# Transistor_controlled_bell_switch.net
KiCad netlist of a schematic drawn in EAGLE
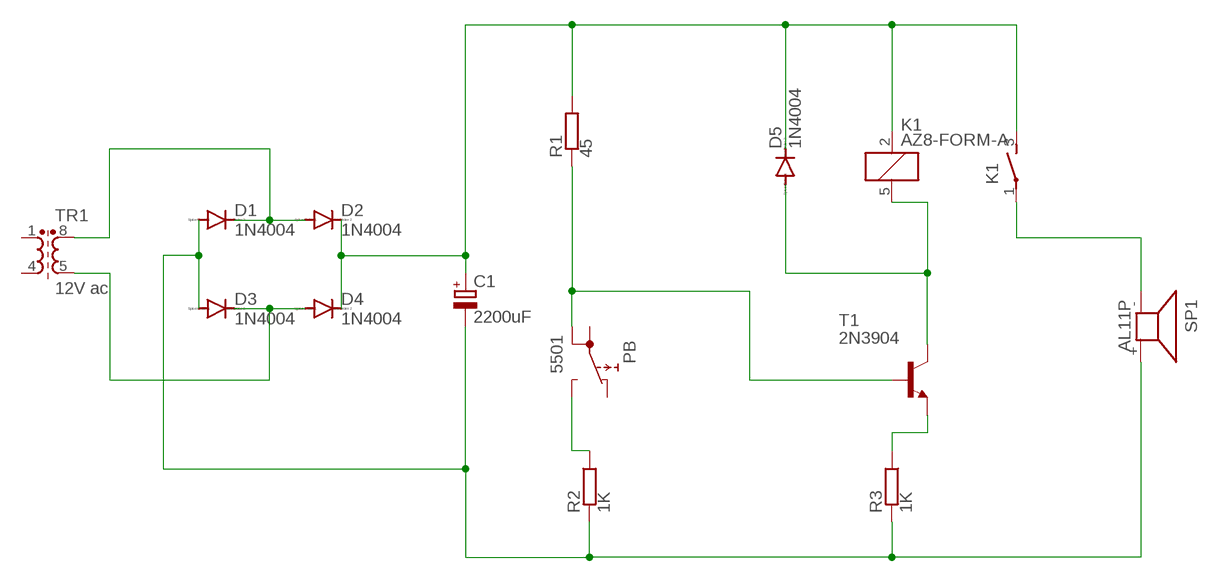
[diagram p0: schematic, sheet 1]

(export (version "E")
  (design (tool "Eeschema 10.0.6"))
  (components
    (comp (ref "C1")
      (value "2200uF")
      (footprint "eagle-import:085CS_1AR")
      (libsource (lib "eagle-import") (part "CPOL-EU085CS-1AR"))
    )
    (comp (ref "D1")
      (value "1N4004")
      (footprint "eagle-import:DO41-10")
      (libsource (lib "eagle-import") (part "1N4004"))
    )
    (comp (ref "D2")
      (value "1N4004")
      (footprint "eagle-import:DO41-10")
      (libsource (lib "eagle-import") (part "1N4004"))
    )
    (comp (ref "D3")
      (value "1N4004")
      (footprint "eagle-import:DO41-10")
      (libsource (lib "eagle-import") (part "1N4004"))
    )
    (comp (ref "D4")
      (value "1N4004")
      (footprint "eagle-import:DO41-10")
      (libsource (lib "eagle-import") (part "1N4004"))
    )
    (comp (ref "D5")
      (value "1N4004")
      (footprint "eagle-import:DO41-10")
      (libsource (lib "eagle-import") (part "1N4004"))
    )
    (comp (ref "K1")
      (value "AZ8-FORM-A")
      (footprint "eagle-import:AZ8")
      (libsource (lib "eagle-import") (part "AZ8-FORM-A"))
    )
    (comp (ref "PB")
      (value "5501")
      (footprint "eagle-import:5501")
      (libsource (lib "eagle-import") (part "55?01"))
    )
    (comp (ref "R1")
      (value "45")
      (footprint "eagle-import:PMD")
      (libsource (lib "eagle-import") (part "PMD"))
    )
    (comp (ref "R2")
      (value "1K")
      (footprint "eagle-import:PMD")
      (libsource (lib "eagle-import") (part "PMD"))
    )
    (comp (ref "R3")
      (value "1K")
      (footprint "eagle-import:PMD")
      (libsource (lib "eagle-import") (part "PMD"))
    )
    (comp (ref "SP1")
      (value "AL11P")
      (footprint "eagle-import:AL11P")
      (libsource (lib "eagle-import") (part "AL11P"))
    )
    (comp (ref "T1")
      (value "2N3904")
      (footprint "eagle-import:TO92")
      (libsource (lib "eagle-import") (part "2N3904"))
    )
    (comp (ref "TR1")
      (value "12V ac")
      (footprint "eagle-import:SM-R6")
      (libsource (lib "eagle-import") (part "SMR6-2W"))
    )
  )
  (nets
    (net (code "1") (name "Net-(D1-PadC)") (class "Default")
      (node (ref "D1") (pin "C") (pinfunction "C_C") (pintype "passive"))
      (node (ref "D2") (pin "A") (pinfunction "A_A") (pintype "passive"))
      (node (ref "TR1") (pin "8") (pinfunction "8_8") (pintype "passive"))
    )
    (net (code "2") (name "Net-(D3-PadC)") (class "Default")
      (node (ref "D3") (pin "C") (pinfunction "C_C") (pintype "passive"))
      (node (ref "D4") (pin "A") (pinfunction "A_A") (pintype "passive"))
      (node (ref "TR1") (pin "5") (pinfunction "5_5") (pintype "passive"))
    )
    (net (code "3") (name "Net-(K1A-P)") (class "Default")
      (node (ref "K1") (pin "1") (pinfunction "P_1") (pintype "passive"))
      (node (ref "SP1") (pin "-") (pinfunction "1_-") (pintype "passive"))
    )
    (net (code "4") (name "Net-(K1A-S)") (class "Default")
      (node (ref "C1") (pin "+") (pinfunction "+_+") (pintype "passive"))
      (node (ref "D2") (pin "C") (pinfunction "C_C") (pintype "passive"))
      (node (ref "D4") (pin "C") (pinfunction "C_C") (pintype "passive"))
      (node (ref "D5") (pin "C") (pinfunction "C_C") (pintype "passive"))
      (node (ref "K1") (pin "2") (pinfunction "1_2") (pintype "passive"))
      (node (ref "K1") (pin "3") (pinfunction "S_3") (pintype "passive"))
      (node (ref "R1") (pin "1") (pinfunction "1_1") (pintype "passive"))
    )
    (net (code "5") (name "Net-(K1B-2)") (class "Default")
      (node (ref "D5") (pin "A") (pinfunction "A_A") (pintype "passive"))
      (node (ref "K1") (pin "5") (pinfunction "2_5") (pintype "passive"))
      (node (ref "T1") (pin "1") (pinfunction "C_1") (pintype "passive"))
    )
    (net (code "6") (name "Net-(PB-PadNO)") (class "Default")
      (node (ref "PB") (pin "NO") (pinfunction "NO_NO") (pintype "passive"))
      (node (ref "R2") (pin "1") (pinfunction "1_1") (pintype "passive"))
    )
    (net (code "7") (name "Net-(SP1-2)") (class "Default")
      (node (ref "C1") (pin "-") (pinfunction "-_-") (pintype "passive"))
      (node (ref "D1") (pin "A") (pinfunction "A_A") (pintype "passive"))
      (node (ref "D3") (pin "A") (pinfunction "A_A") (pintype "passive"))
      (node (ref "R2") (pin "2") (pinfunction "2_2") (pintype "passive"))
      (node (ref "R3") (pin "2") (pinfunction "2_2") (pintype "passive"))
      (node (ref "SP1") (pin "+") (pinfunction "2_+") (pintype "passive"))
    )
    (net (code "8") (name "Net-(T1-B)") (class "Default")
      (node (ref "PB") (pin "1B") (pinfunction "1B_1B") (pintype "passive"))
      (node (ref "R1") (pin "2") (pinfunction "2_2") (pintype "passive"))
      (node (ref "T1") (pin "2") (pinfunction "B_2") (pintype "passive"))
    )
    (net (code "9") (name "Net-(T1-E)") (class "Default")
      (node (ref "R3") (pin "1") (pinfunction "1_1") (pintype "passive"))
      (node (ref "T1") (pin "3") (pinfunction "E_3") (pintype "passive"))
    )
    (net (code "10") (name "unconnected-(PB-Pad1A)") (class "Default")
      (node (ref "PB") (pin "1A") (pinfunction "1A_1A") (pintype "passive"))
    )
    (net (code "11") (name "unconnected-(PB-PadNC)") (class "Default")
      (node (ref "PB") (pin "NC") (pinfunction "NC_NC") (pintype "passive"))
    )
    (net (code "12") (name "unconnected-(TR1-Pad1)") (class "Default")
      (node (ref "TR1") (pin "1") (pinfunction "1_1") (pintype "passive"))
    )
    (net (code "13") (name "unconnected-(TR1-Pad4)") (class "Default")
      (node (ref "TR1") (pin "4") (pinfunction "4_4") (pintype "passive"))
    )
  )
)
